# CurrentMonitorOnAStick.net
KiCad netlist of a schematic drawn in EAGLE
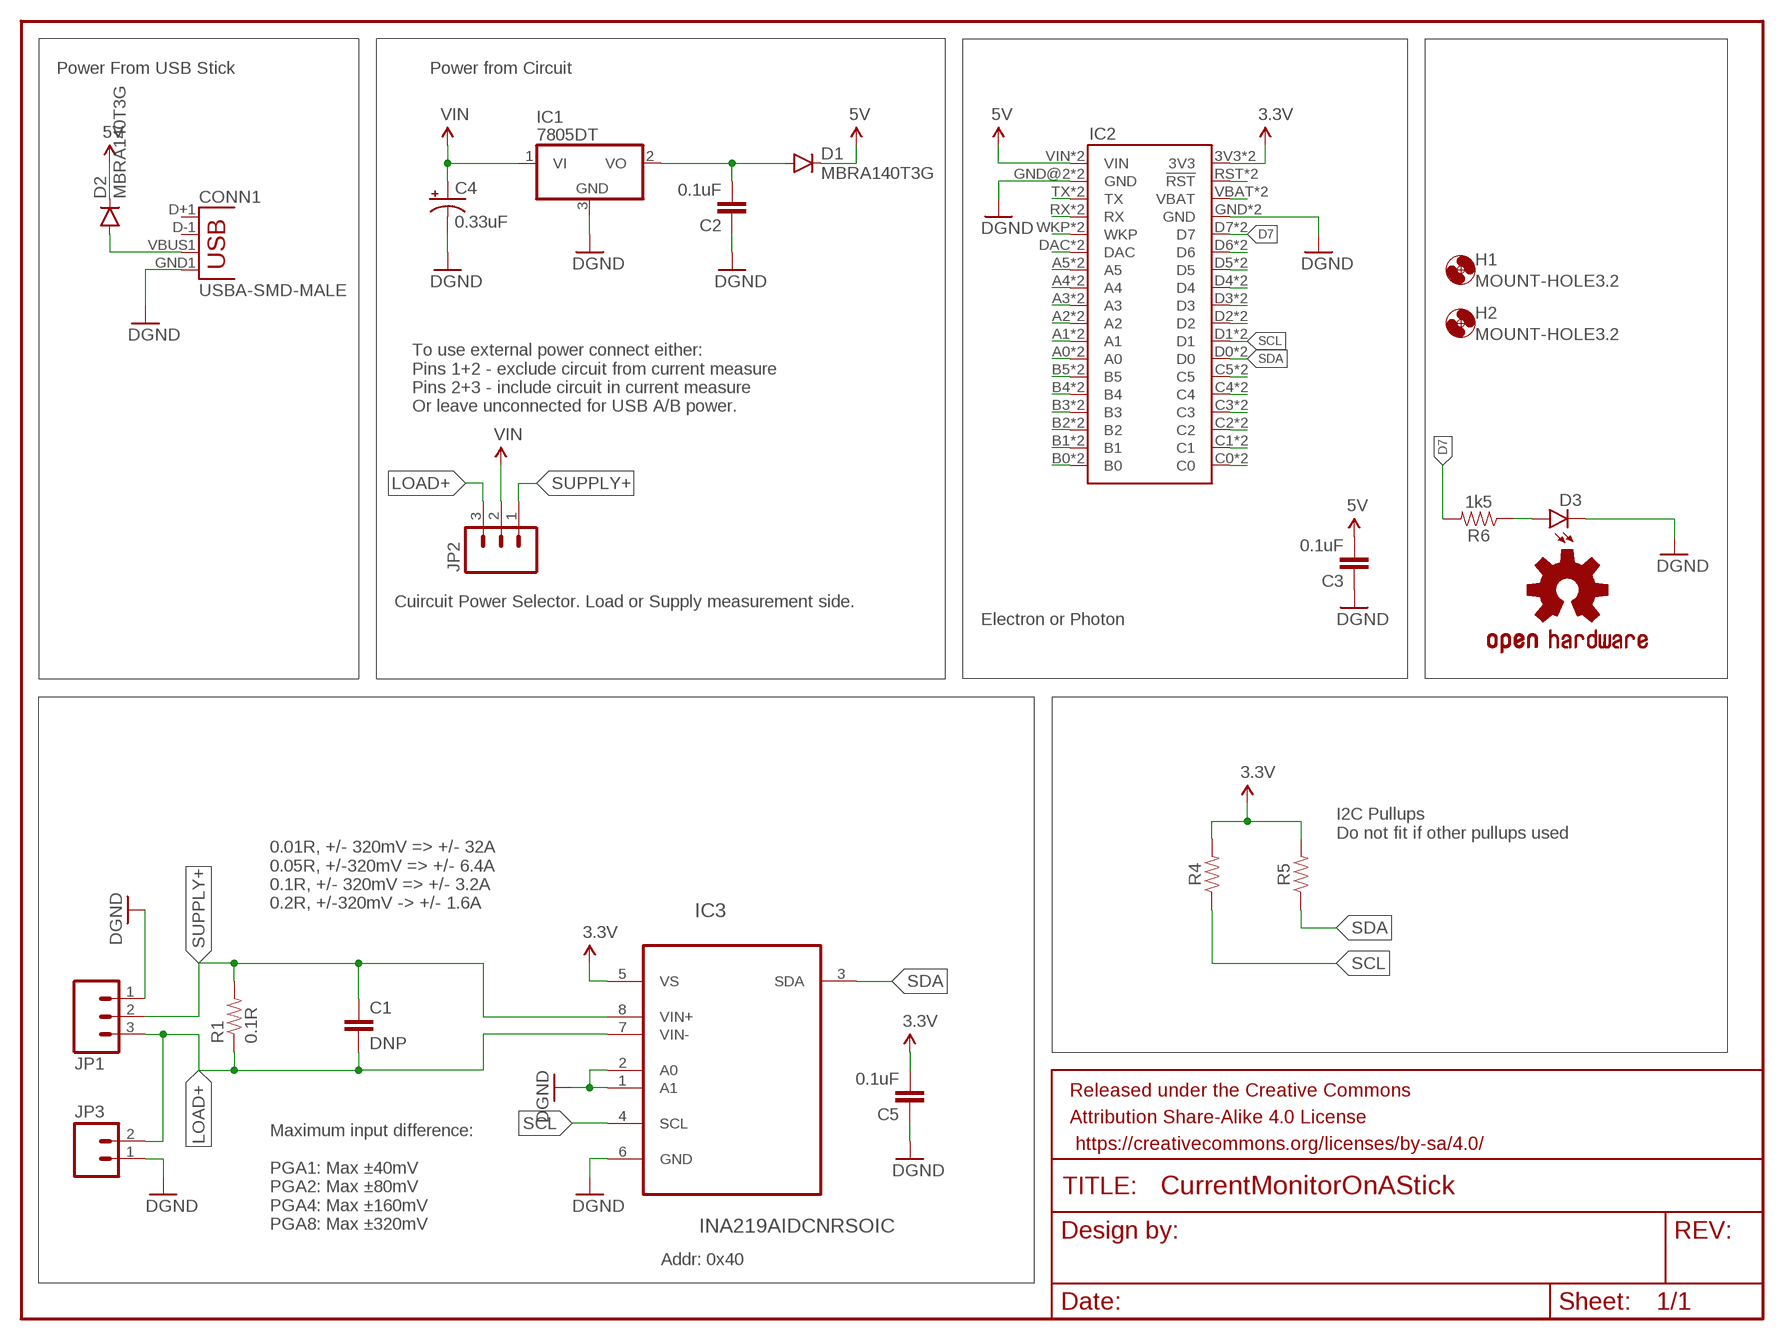
[diagram p0: schematic, sheet 1]

(export (version "E")
  (design (tool "Eeschema 10.0.6"))
  (components
    (comp (ref "C1")
      (value "DNP")
      (footprint "eagle-import:0805")
      (libsource (lib "eagle-import") (part "CAP0805"))
    )
    (comp (ref "C2")
      (value "0.1uF")
      (footprint "eagle-import:0805")
      (libsource (lib "eagle-import") (part "SparkFun-Passives_CAP0805"))
    )
    (comp (ref "C3")
      (value "0.1uF")
      (footprint "eagle-import:0805")
      (libsource (lib "eagle-import") (part "SparkFun-Passives_CAP0805"))
    )
    (comp (ref "C4")
      (value "0.33uF")
      (footprint "eagle-import:EIA3216")
      (libsource (lib "eagle-import") (part "10UF-16V-10%(TANT)"))
    )
    (comp (ref "C5")
      (value "0.1uF")
      (footprint "eagle-import:0805")
      (libsource (lib "eagle-import") (part "SparkFun-Passives_CAP0805"))
    )
    (comp (ref "CONN1")
      (value "USBA-SMD-MALE")
      (footprint "eagle-import:USB-A-SMT-MALE")
      (libsource (lib "eagle-import") (part "USBA-SMD-MALE"))
    )
    (comp (ref "D1")
      (value "MBRA140T3G")
      (footprint "eagle-import:SMA-DIODE")
      (libsource (lib "eagle-import") (part "DIODESMA"))
    )
    (comp (ref "D2")
      (value "MBRA140T3G")
      (footprint "eagle-import:SMA-DIODE")
      (libsource (lib "eagle-import") (part "DIODESMA"))
    )
    (comp (ref "D3")
      (value "LED1206-BOTTOM")
      (footprint "eagle-import:LED-1206-BOTTOM")
      (libsource (lib "eagle-import") (part "LED1206-BOTTOM"))
    )
    (comp (ref "FRAME2")
      (value "FRAME-LETTER")
      (footprint "eagle-import:CREATIVE_COMMONS")
      (libsource (lib "eagle-import") (part "FRAME-LETTER"))
    )
    (comp (ref "H1")
      (value "MOUNT-HOLE3.2")
      (footprint "eagle-import:3,2")
      (libsource (lib "eagle-import") (part "MOUNT-HOLE3.2"))
    )
    (comp (ref "H2")
      (value "MOUNT-HOLE3.2")
      (footprint "eagle-import:3,2")
      (libsource (lib "eagle-import") (part "MOUNT-HOLE3.2"))
    )
    (comp (ref "IC1")
      (value "7805DT")
      (footprint "eagle-import:TO252")
      (libsource (lib "eagle-import") (part "78DT05"))
    )
    (comp (ref "IC2")
      (value "ELECTRONDUALNAMED")
      (footprint "eagle-import:ELECTRON_SIMPLE_SILK_NAMES_DUAL")
      (libsource (lib "eagle-import") (part "ELECTRONDUALNAMED"))
    )
    (comp (ref "IC3")
      (value "INA219AIDCNRSOIC")
      (footprint "eagle-import:SO08")
      (libsource (lib "eagle-import") (part "INA219AIDCNRSOIC"))
    )
    (comp (ref "JP1")
      (value "M03-SCREW-5MM")
      (footprint "eagle-import:SCREWTERMINAL-5MM-3")
      (libsource (lib "eagle-import") (part "M03-SCREW-5MM"))
    )
    (comp (ref "JP2")
      (value "M03PTH")
      (footprint "eagle-import:1X03")
      (libsource (lib "eagle-import") (part "M03PTH"))
    )
    (comp (ref "JP3")
      (value "M025MM")
      (footprint "eagle-import:SCREWTERMINAL-5MM-2")
      (libsource (lib "eagle-import") (part "M025MM"))
    )
    (comp (ref "LOGO1")
      (value "OSHW-LOGOM")
      (footprint "eagle-import:OSHW-LOGO-M")
      (libsource (lib "eagle-import") (part "OSHW-LOGOM"))
    )
    (comp (ref "R1")
      (value "0.1R")
      (footprint "eagle-import:2512")
      (libsource (lib "eagle-import") (part "0.001OHM-3W-1%(2512)3W/1%"))
    )
    (comp (ref "R4")
      (value "RESISTOR0805")
      (footprint "eagle-import:0805")
      (libsource (lib "eagle-import") (part "RESISTOR0805"))
    )
    (comp (ref "R5")
      (value "RESISTOR0805")
      (footprint "eagle-import:0805")
      (libsource (lib "eagle-import") (part "RESISTOR0805"))
    )
    (comp (ref "R6")
      (value "1k5")
      (footprint "eagle-import:0805")
      (libsource (lib "eagle-import") (part "RESISTOR0805"))
    )
  )
  (nets
    (net (code "1") (name "3.3V") (class "Default")
      (node (ref "C5") (pin "2") (pinfunction "2_2") (pintype "passive"))
      (node (ref "IC2") (pin "3V3") (pinfunction "3V3_3V3") (pintype "power_in"))
      (node (ref "IC2") (pin "3V3_1") (pinfunction "3V3_3V3_1") (pintype "power_in"))
      (node (ref "IC3") (pin "5") (pinfunction "VS_5") (pintype "power_in"))
      (node (ref "R4") (pin "2") (pinfunction "2_2") (pintype "passive"))
      (node (ref "R5") (pin "2") (pinfunction "2_2") (pintype "passive"))
    )
    (net (code "2") (name "5V") (class "Default")
      (node (ref "C3") (pin "2") (pinfunction "2_2") (pintype "passive"))
      (node (ref "D1") (pin "C") (pinfunction "C_C") (pintype "passive"))
      (node (ref "D2") (pin "C") (pinfunction "C_C") (pintype "passive"))
      (node (ref "IC2") (pin "VIN") (pinfunction "VIN_VIN") (pintype "power_in"))
      (node (ref "IC2") (pin "VIN_1B") (pinfunction "VIN_VIN_1B") (pintype "power_in"))
    )
    (net (code "3") (name "D7") (class "Default")
      (node (ref "IC2") (pin "D7") (pinfunction "D7_D7") (pintype "bidirectional"))
      (node (ref "IC2") (pin "D7_1") (pinfunction "D7_D7_1") (pintype "bidirectional"))
      (node (ref "R6") (pin "2") (pinfunction "2_2") (pintype "passive"))
    )
    (net (code "4") (name "DGND") (class "Default")
      (node (ref "C2") (pin "1") (pinfunction "1_1") (pintype "passive"))
      (node (ref "C3") (pin "1") (pinfunction "1_1") (pintype "passive"))
      (node (ref "C4") (pin "C") (pinfunction "-_C") (pintype "passive"))
      (node (ref "C5") (pin "1") (pinfunction "1_1") (pintype "passive"))
      (node (ref "CONN1") (pin "GND1") (pinfunction "GND_GND1") (pintype "bidirectional"))
      (node (ref "D3") (pin "C") (pinfunction "C_C") (pintype "passive"))
      (node (ref "IC1") (pin "3") (pinfunction "GND_3") (pintype "passive"))
      (node (ref "IC2") (pin "GND") (pinfunction "GND_GND") (pintype "power_in"))
      (node (ref "IC2") (pin "GND@2") (pinfunction "GND_GND@2") (pintype "power_in"))
      (node (ref "IC2") (pin "GND_1") (pinfunction "GND_GND_1") (pintype "power_in"))
      (node (ref "IC2") (pin "GND_1B") (pinfunction "GND_GND_1B") (pintype "power_in"))
      (node (ref "IC3") (pin "1") (pinfunction "A1_1") (pintype "input"))
      (node (ref "IC3") (pin "2") (pinfunction "A0_2") (pintype "input"))
      (node (ref "IC3") (pin "6") (pinfunction "GND_6") (pintype "passive"))
      (node (ref "JP1") (pin "1") (pinfunction "1_1") (pintype "passive"))
      (node (ref "JP3") (pin "1") (pinfunction "1_1") (pintype "passive"))
    )
    (net (code "5") (name "LOAD+") (class "Default")
      (node (ref "C1") (pin "2") (pinfunction "2_2") (pintype "passive"))
      (node (ref "IC3") (pin "7") (pinfunction "VIN-_7") (pintype "input"))
      (node (ref "JP1") (pin "3") (pinfunction "3_3") (pintype "passive"))
      (node (ref "JP2") (pin "3") (pinfunction "3_3") (pintype "passive"))
      (node (ref "JP3") (pin "2") (pinfunction "2_2") (pintype "passive"))
      (node (ref "R1") (pin "1") (pinfunction "1_1") (pintype "passive"))
    )
    (net (code "6") (name "Net-(CONN1-VBUS)") (class "Default")
      (node (ref "CONN1") (pin "VBUS1") (pinfunction "VBUS_VBUS1") (pintype "bidirectional"))
      (node (ref "D2") (pin "A") (pinfunction "A_A") (pintype "passive"))
    )
    (net (code "7") (name "Net-(D3-PadA)") (class "Default")
      (node (ref "D3") (pin "A") (pinfunction "A_A") (pintype "passive"))
      (node (ref "R6") (pin "1") (pinfunction "1_1") (pintype "passive"))
    )
    (net (code "8") (name "Net-(IC1-VO)") (class "Default")
      (node (ref "C2") (pin "2") (pinfunction "2_2") (pintype "passive"))
      (node (ref "D1") (pin "A") (pinfunction "A_A") (pintype "passive"))
      (node (ref "IC1") (pin "2") (pinfunction "VO_2") (pintype "passive"))
    )
    (net (code "9") (name "Net-(IC2-A0-PadA0_1)") (class "Default")
      (node (ref "IC2") (pin "A0") (pinfunction "A0_A0") (pintype "bidirectional"))
      (node (ref "IC2") (pin "A0_1") (pinfunction "A0_A0_1") (pintype "bidirectional"))
    )
    (net (code "10") (name "Net-(IC2-A1-PadA1_1)") (class "Default")
      (node (ref "IC2") (pin "A1") (pinfunction "A1_A1") (pintype "bidirectional"))
      (node (ref "IC2") (pin "A1_1") (pinfunction "A1_A1_1") (pintype "bidirectional"))
    )
    (net (code "11") (name "Net-(IC2-A2-PadA2_1)") (class "Default")
      (node (ref "IC2") (pin "A2") (pinfunction "A2_A2") (pintype "bidirectional"))
      (node (ref "IC2") (pin "A2_1") (pinfunction "A2_A2_1") (pintype "bidirectional"))
    )
    (net (code "12") (name "Net-(IC2-A3-PadA3_1)") (class "Default")
      (node (ref "IC2") (pin "A3") (pinfunction "A3_A3") (pintype "bidirectional"))
      (node (ref "IC2") (pin "A3_1") (pinfunction "A3_A3_1") (pintype "bidirectional"))
    )
    (net (code "13") (name "Net-(IC2-A4-PadA4_1)") (class "Default")
      (node (ref "IC2") (pin "A4") (pinfunction "A4_A4") (pintype "bidirectional"))
      (node (ref "IC2") (pin "A4_1") (pinfunction "A4_A4_1") (pintype "bidirectional"))
    )
    (net (code "14") (name "Net-(IC2-A5-PadA5_1)") (class "Default")
      (node (ref "IC2") (pin "A5") (pinfunction "A5_A5") (pintype "bidirectional"))
      (node (ref "IC2") (pin "A5_1") (pinfunction "A5_A5_1") (pintype "bidirectional"))
    )
    (net (code "15") (name "Net-(IC2-B0-PadB0_1)") (class "Default")
      (node (ref "IC2") (pin "B0") (pinfunction "B0_B0") (pintype "bidirectional"))
      (node (ref "IC2") (pin "B0_1") (pinfunction "B0_B0_1") (pintype "bidirectional"))
    )
    (net (code "16") (name "Net-(IC2-B1-PadB1_1)") (class "Default")
      (node (ref "IC2") (pin "B1") (pinfunction "B1_B1") (pintype "bidirectional"))
      (node (ref "IC2") (pin "B1_1") (pinfunction "B1_B1_1") (pintype "bidirectional"))
    )
    (net (code "17") (name "Net-(IC2-B2-PadB2_1)") (class "Default")
      (node (ref "IC2") (pin "B2") (pinfunction "B2_B2") (pintype "bidirectional"))
      (node (ref "IC2") (pin "B2_1") (pinfunction "B2_B2_1") (pintype "bidirectional"))
    )
    (net (code "18") (name "Net-(IC2-B3-PadB3_1)") (class "Default")
      (node (ref "IC2") (pin "B3") (pinfunction "B3_B3") (pintype "bidirectional"))
      (node (ref "IC2") (pin "B3_1") (pinfunction "B3_B3_1") (pintype "bidirectional"))
    )
    (net (code "19") (name "Net-(IC2-B4-PadB4_1)") (class "Default")
      (node (ref "IC2") (pin "B4") (pinfunction "B4_B4") (pintype "bidirectional"))
      (node (ref "IC2") (pin "B4_1") (pinfunction "B4_B4_1") (pintype "bidirectional"))
    )
    (net (code "20") (name "Net-(IC2-B5-PadB5_1)") (class "Default")
      (node (ref "IC2") (pin "B5") (pinfunction "B5_B5") (pintype "bidirectional"))
      (node (ref "IC2") (pin "B5_1") (pinfunction "B5_B5_1") (pintype "bidirectional"))
    )
    (net (code "21") (name "Net-(IC2-C0-PadC0_1)") (class "Default")
      (node (ref "IC2") (pin "C0") (pinfunction "C0_C0") (pintype "bidirectional"))
      (node (ref "IC2") (pin "C0_1") (pinfunction "C0_C0_1") (pintype "bidirectional"))
    )
    (net (code "22") (name "Net-(IC2-C1-PadC1_1)") (class "Default")
      (node (ref "IC2") (pin "C1") (pinfunction "C1_C1") (pintype "bidirectional"))
      (node (ref "IC2") (pin "C1_1") (pinfunction "C1_C1_1") (pintype "bidirectional"))
    )
    (net (code "23") (name "Net-(IC2-C2-PadC2_1)") (class "Default")
      (node (ref "IC2") (pin "C2") (pinfunction "C2_C2") (pintype "bidirectional"))
      (node (ref "IC2") (pin "C2_1") (pinfunction "C2_C2_1") (pintype "bidirectional"))
    )
    (net (code "24") (name "Net-(IC2-C3-PadC3_1)") (class "Default")
      (node (ref "IC2") (pin "C3") (pinfunction "C3_C3") (pintype "bidirectional"))
      (node (ref "IC2") (pin "C3_1") (pinfunction "C3_C3_1") (pintype "bidirectional"))
    )
    (net (code "25") (name "Net-(IC2-C4-PadC4_1)") (class "Default")
      (node (ref "IC2") (pin "C4") (pinfunction "C4_C4") (pintype "bidirectional"))
      (node (ref "IC2") (pin "C4_1") (pinfunction "C4_C4_1") (pintype "bidirectional"))
    )
    (net (code "26") (name "Net-(IC2-C5-PadC5_1)") (class "Default")
      (node (ref "IC2") (pin "C5") (pinfunction "C5_C5") (pintype "bidirectional"))
      (node (ref "IC2") (pin "C5_1") (pinfunction "C5_C5_1") (pintype "bidirectional"))
    )
    (net (code "27") (name "Net-(IC2-D2-PadD2_1)") (class "Default")
      (node (ref "IC2") (pin "D2") (pinfunction "D2_D2") (pintype "bidirectional"))
      (node (ref "IC2") (pin "D2_1") (pinfunction "D2_D2_1") (pintype "bidirectional"))
    )
    (net (code "28") (name "Net-(IC2-D3-PadD3_1)") (class "Default")
      (node (ref "IC2") (pin "D3") (pinfunction "D3_D3") (pintype "bidirectional"))
      (node (ref "IC2") (pin "D3_1") (pinfunction "D3_D3_1") (pintype "bidirectional"))
    )
    (net (code "29") (name "Net-(IC2-D4-PadD4_1)") (class "Default")
      (node (ref "IC2") (pin "D4") (pinfunction "D4_D4") (pintype "bidirectional"))
      (node (ref "IC2") (pin "D4_1") (pinfunction "D4_D4_1") (pintype "bidirectional"))
    )
    (net (code "30") (name "Net-(IC2-D5-PadD5_1)") (class "Default")
      (node (ref "IC2") (pin "D5") (pinfunction "D5_D5") (pintype "bidirectional"))
      (node (ref "IC2") (pin "D5_1") (pinfunction "D5_D5_1") (pintype "bidirectional"))
    )
    (net (code "31") (name "Net-(IC2-D6-PadD6_1)") (class "Default")
      (node (ref "IC2") (pin "D6") (pinfunction "D6_D6") (pintype "bidirectional"))
      (node (ref "IC2") (pin "D6_1") (pinfunction "D6_D6_1") (pintype "bidirectional"))
    )
    (net (code "32") (name "Net-(IC2-DAC-PadDAC_1)") (class "Default")
      (node (ref "IC2") (pin "DAC") (pinfunction "DAC_DAC") (pintype "bidirectional"))
      (node (ref "IC2") (pin "DAC_1") (pinfunction "DAC_DAC_1") (pintype "bidirectional"))
    )
    (net (code "33") (name "Net-(IC2-PadRX)") (class "Default")
      (node (ref "IC2") (pin "RX") (pinfunction "RX_RX") (pintype "bidirectional"))
      (node (ref "IC2") (pin "RX_1") (pinfunction "RX_RX_1") (pintype "bidirectional"))
    )
    (net (code "34") (name "Net-(IC2-PadTX)") (class "Default")
      (node (ref "IC2") (pin "TX") (pinfunction "TX_TX") (pintype "bidirectional"))
      (node (ref "IC2") (pin "TX_1") (pinfunction "TX_TX_1") (pintype "bidirectional"))
    )
    (net (code "35") (name "Net-(IC2-PadVBAT)") (class "Default")
      (node (ref "IC2") (pin "VBAT") (pinfunction "VBAT_VBAT") (pintype "passive"))
      (node (ref "IC2") (pin "VBATT_1") (pinfunction "VBAT_VBATT_1") (pintype "passive"))
    )
    (net (code "36") (name "Net-(IC2-PadWKP)") (class "Default")
      (node (ref "IC2") (pin "WKP") (pinfunction "WKP_WKP") (pintype "bidirectional"))
      (node (ref "IC2") (pin "WKP_1") (pinfunction "WKP_WKP_1") (pintype "bidirectional"))
    )
    (net (code "37") (name "Net-(IC2-~{RST}-PadRST)") (class "Default")
      (node (ref "IC2") (pin "RST") (pinfunction "~{RST}_RST") (pintype "bidirectional"))
      (node (ref "IC2") (pin "RST_1") (pinfunction "~{RST}_RST_1") (pintype "bidirectional"))
    )
    (net (code "38") (name "SCL") (class "Default")
      (node (ref "IC2") (pin "D1") (pinfunction "D1_D1") (pintype "bidirectional"))
      (node (ref "IC2") (pin "D1_1") (pinfunction "D1_D1_1") (pintype "bidirectional"))
      (node (ref "IC3") (pin "4") (pinfunction "SCL_4") (pintype "input"))
      (node (ref "R4") (pin "1") (pinfunction "1_1") (pintype "passive"))
    )
    (net (code "39") (name "SDA") (class "Default")
      (node (ref "IC2") (pin "D0") (pinfunction "D0_D0") (pintype "bidirectional"))
      (node (ref "IC2") (pin "D0_1") (pinfunction "D0_D0_1") (pintype "bidirectional"))
      (node (ref "IC3") (pin "3") (pinfunction "SDA_3") (pintype "bidirectional"))
      (node (ref "R5") (pin "1") (pinfunction "1_1") (pintype "passive"))
    )
    (net (code "40") (name "SUPPLY+") (class "Default")
      (node (ref "C1") (pin "1") (pinfunction "1_1") (pintype "passive"))
      (node (ref "IC3") (pin "8") (pinfunction "VIN+_8") (pintype "input"))
      (node (ref "JP1") (pin "2") (pinfunction "2_2") (pintype "passive"))
      (node (ref "JP2") (pin "1") (pinfunction "1_1") (pintype "passive"))
      (node (ref "R1") (pin "2") (pinfunction "2_2") (pintype "passive"))
    )
    (net (code "41") (name "VIN") (class "Default")
      (node (ref "C4") (pin "A") (pinfunction "+_A") (pintype "passive"))
      (node (ref "IC1") (pin "1") (pinfunction "VI_1") (pintype "input"))
      (node (ref "JP2") (pin "2") (pinfunction "2_2") (pintype "passive"))
    )
    (net (code "42") (name "unconnected-(CONN1-D+-PadD+1)") (class "Default")
      (node (ref "CONN1") (pin "D+1") (pinfunction "D+_D+1") (pintype "bidirectional"))
    )
    (net (code "43") (name "unconnected-(CONN1-D--PadD-1)") (class "Default")
      (node (ref "CONN1") (pin "D-1") (pinfunction "D-_D-1") (pintype "bidirectional"))
    )
  )
)
